# axiom_beta_interface_dummy_v0_13_8a810f7.net
KiCad netlist of a schematic drawn in EAGLE
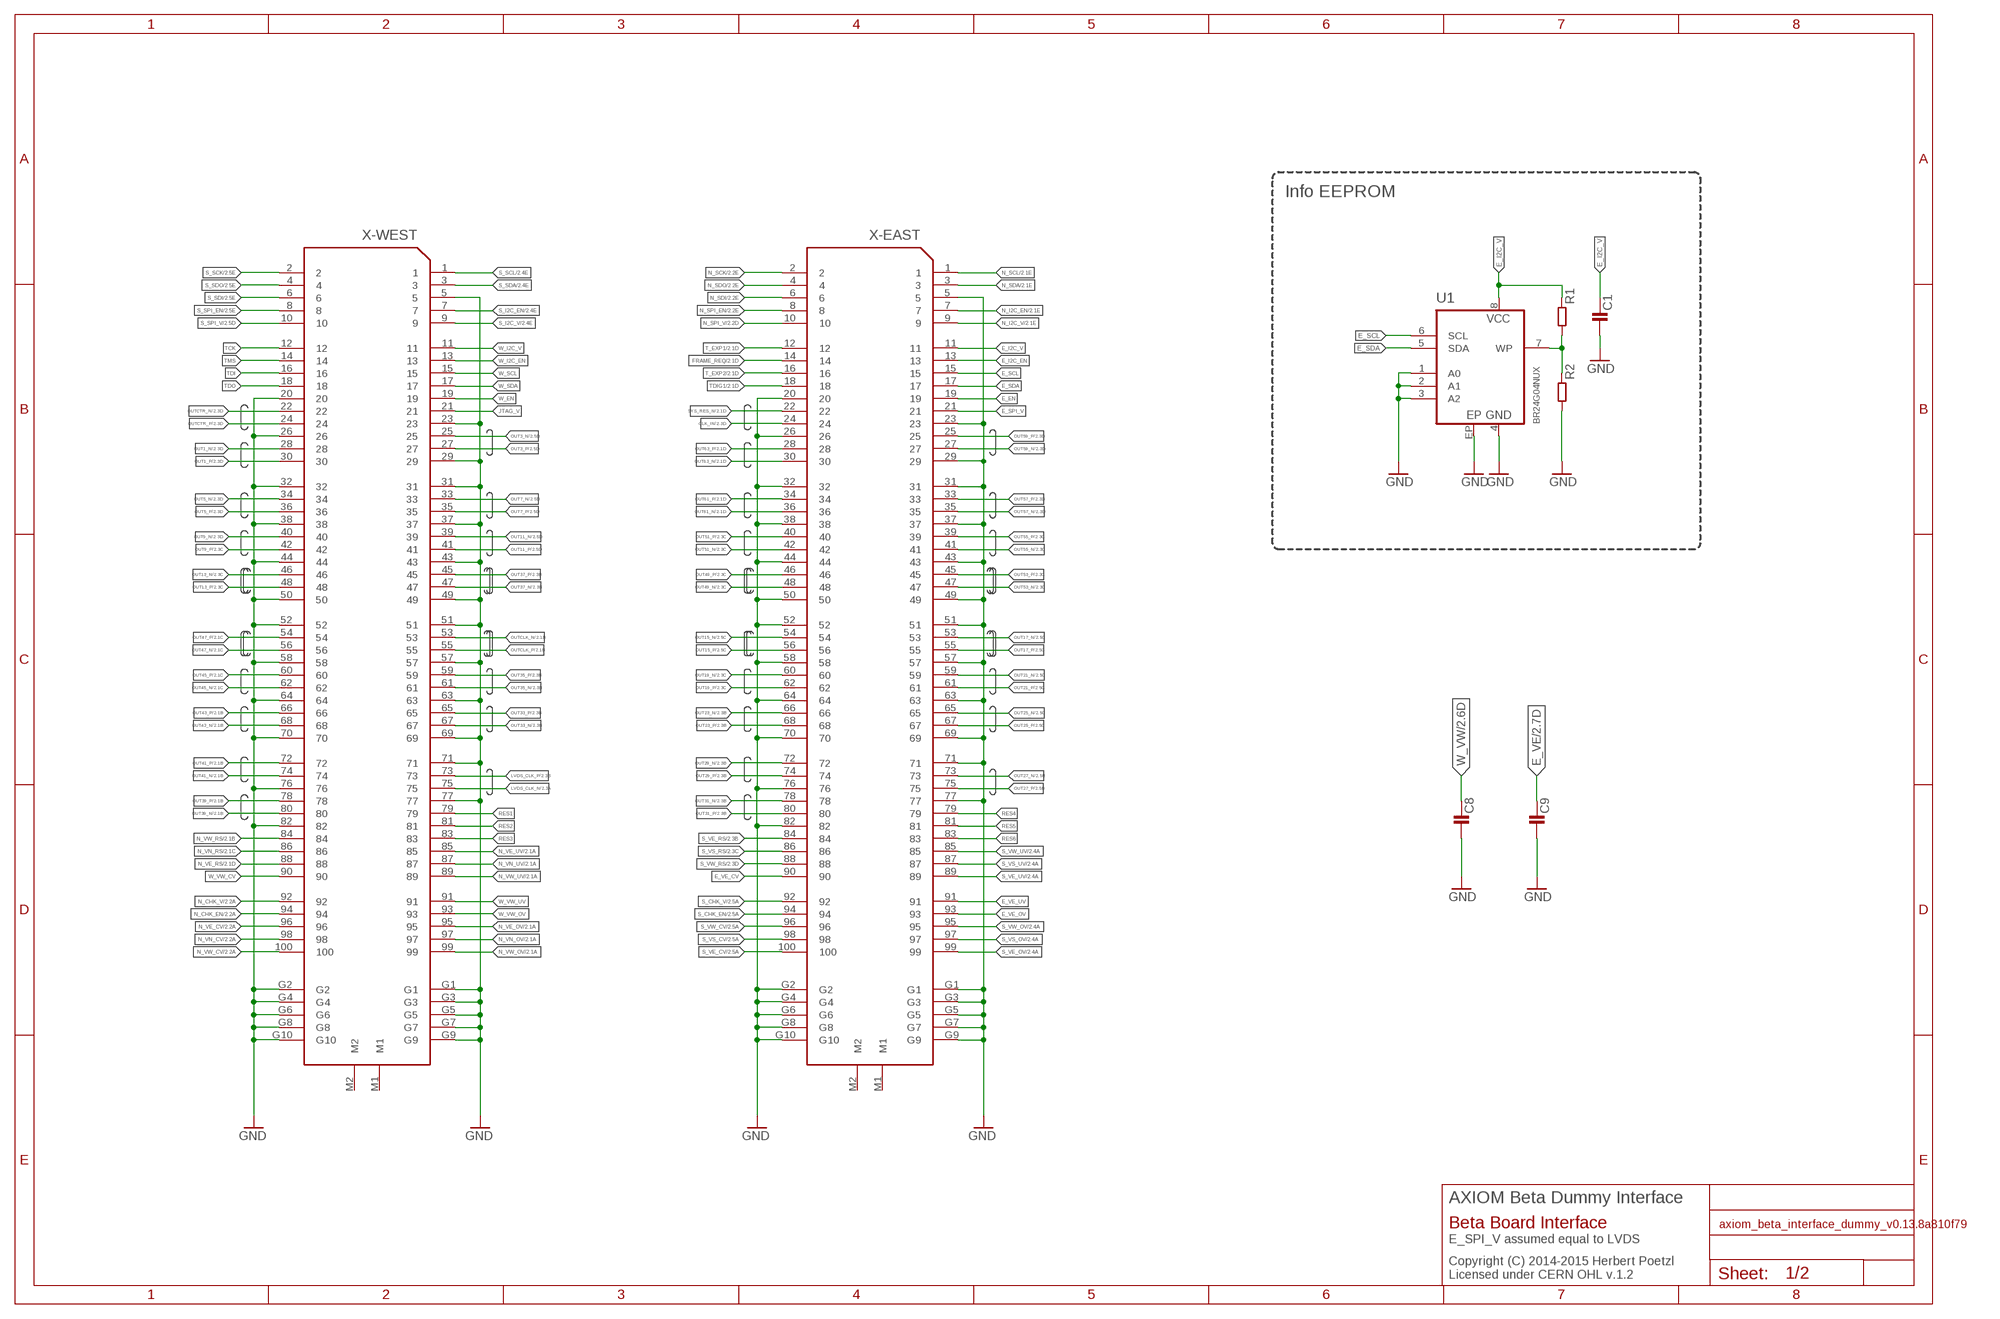
[diagram p0: schematic, sheet 1]
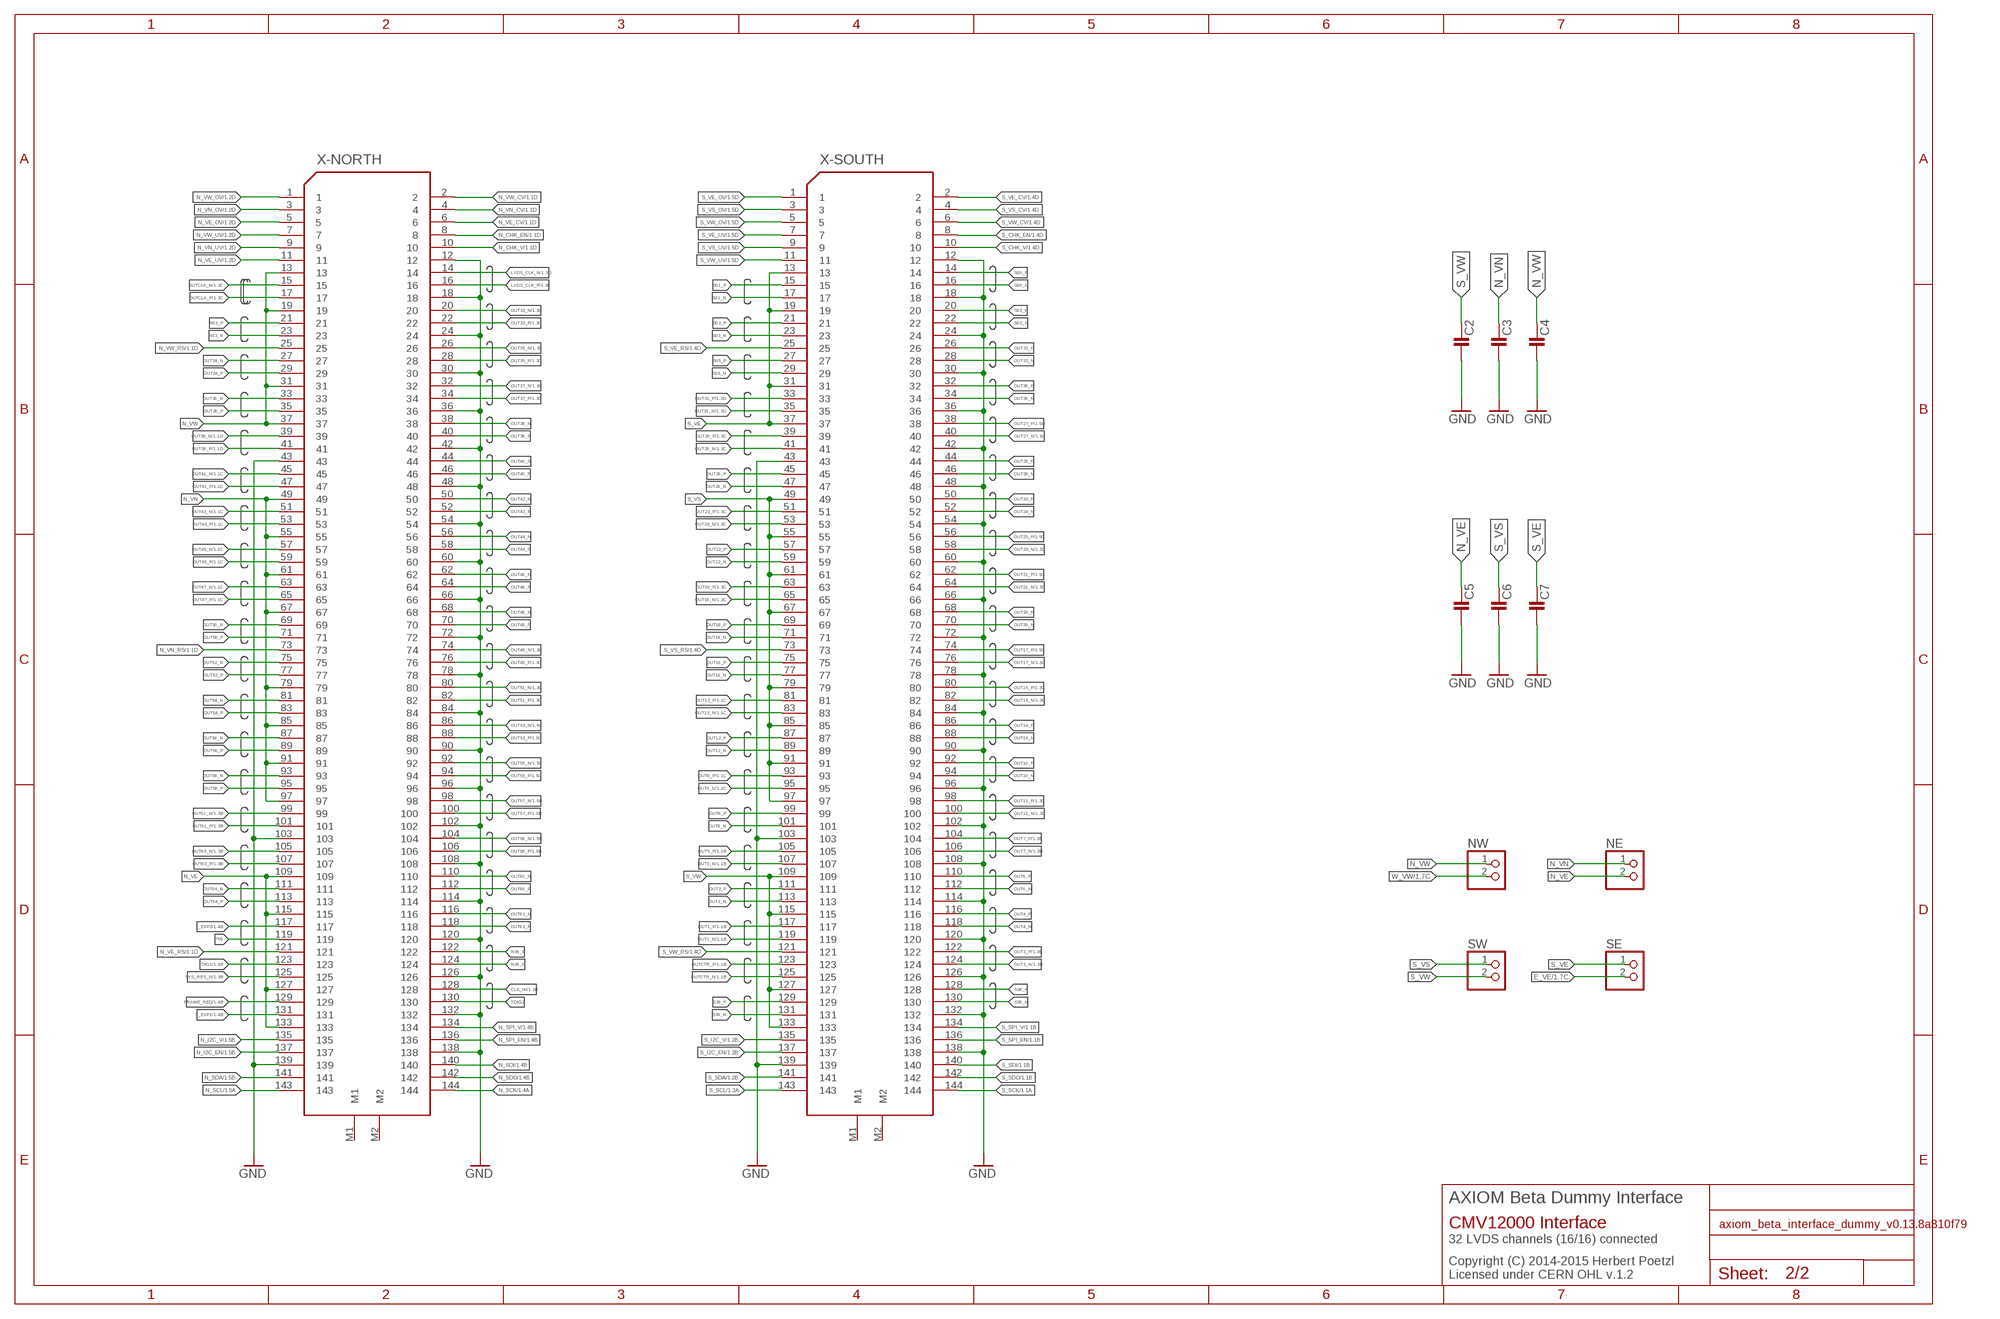
[diagram p1: schematic, sheet 2]

(export (version "E")
  (design (tool "Eeschema 10.0.6"))
  (components
    (comp (ref "C2")
      (value "C0805-B")
      (footprint "eagle-import:0805-B")
      (libsource (lib "eagle-import") (part "C0805-B"))
    )
    (comp (ref "C3")
      (value "C0805-B")
      (footprint "eagle-import:0805-B")
      (libsource (lib "eagle-import") (part "C0805-B"))
    )
    (comp (ref "C4")
      (value "C0805-B")
      (footprint "eagle-import:0805-B")
      (libsource (lib "eagle-import") (part "C0805-B"))
    )
    (comp (ref "C5")
      (value "C0805-B")
      (footprint "eagle-import:0805-B")
      (libsource (lib "eagle-import") (part "C0805-B"))
    )
    (comp (ref "C6")
      (value "C0805-B")
      (footprint "eagle-import:0805-B")
      (libsource (lib "eagle-import") (part "C0805-B"))
    )
    (comp (ref "C7")
      (value "C0805-B")
      (footprint "eagle-import:0805-B")
      (libsource (lib "eagle-import") (part "C0805-B"))
    )
    (comp (ref "NE")
      (value "PINHD-1X02_2.54")
      (footprint "eagle-import:1X02")
      (libsource (lib "eagle-import") (part "PINHD-1X02_2.54"))
    )
    (comp (ref "NW")
      (value "PINHD-1X02_2.54")
      (footprint "eagle-import:1X02")
      (libsource (lib "eagle-import") (part "PINHD-1X02_2.54"))
    )
    (comp (ref "SE")
      (value "PINHD-1X02_2.54")
      (footprint "eagle-import:1X02")
      (libsource (lib "eagle-import") (part "PINHD-1X02_2.54"))
    )
    (comp (ref "SW")
      (value "PINHD-1X02_2.54")
      (footprint "eagle-import:1X02")
      (libsource (lib "eagle-import") (part "PINHD-1X02_2.54"))
    )
    (comp (ref "X-NORTH")
      (value "FX10-144S")
      (footprint "eagle-import:FX10A-144S")
      (libsource (lib "eagle-import") (part "FX10-144S"))
    )
    (comp (ref "X-SOUTH")
      (value "FX10-144S")
      (footprint "eagle-import:FX10A-144S")
      (libsource (lib "eagle-import") (part "FX10-144S"))
    )
    (comp (ref "C1")
      (value "C0402-B")
      (footprint "eagle-import:0402-B")
      (libsource (lib "eagle-import") (part "C0402-B"))
    )
    (comp (ref "C8")
      (value "C0805-B")
      (footprint "eagle-import:0805-B")
      (libsource (lib "eagle-import") (part "C0805-B"))
    )
    (comp (ref "C9")
      (value "C0805-B")
      (footprint "eagle-import:0805-B")
      (libsource (lib "eagle-import") (part "C0805-B"))
    )
    (comp (ref "R1")
      (value "R0402-B")
      (footprint "eagle-import:0402-B")
      (libsource (lib "eagle-import") (part "R0402-B"))
    )
    (comp (ref "R2")
      (value "R0402-B")
      (footprint "eagle-import:0402-B")
      (libsource (lib "eagle-import") (part "R0402-B"))
    )
    (comp (ref "U1")
      (value "BR24G04NUX")
      (footprint "eagle-import:DFN200X300X100-9N")
      (libsource (lib "eagle-import") (part "BR24G04NUX"))
    )
    (comp (ref "X-EAST")
      (value "FX10-100/10P")
      (footprint "eagle-import:FX10A-100P_10")
      (libsource (lib "eagle-import") (part "FX10-100/10P"))
    )
    (comp (ref "X-WEST")
      (value "FX10-100/10P")
      (footprint "eagle-import:FX10A-100P_10")
      (libsource (lib "eagle-import") (part "FX10-100/10P"))
    )
  )
  (nets
    (net (code "1") (name "CLK_IN") (class "Default")
      (node (ref "X-EAST") (pin "24") (pinfunction "24_24") (pintype "bidirectional"))
      (node (ref "X-NORTH") (pin "128") (pinfunction "128_128") (pintype "bidirectional"))
    )
    (net (code "2") (name "E_EN") (class "Default")
      (node (ref "X-EAST") (pin "19") (pinfunction "19_19") (pintype "bidirectional"))
    )
    (net (code "3") (name "E_I2C_EN") (class "Default")
      (node (ref "X-EAST") (pin "13") (pinfunction "13_13") (pintype "bidirectional"))
    )
    (net (code "4") (name "E_I2C_V") (class "Default")
      (node (ref "C1") (pin "1") (pinfunction "1_1") (pintype "passive"))
      (node (ref "R1") (pin "1") (pinfunction "1_1") (pintype "passive"))
      (node (ref "U1") (pin "8") (pinfunction "VCC_8") (pintype "power_in"))
      (node (ref "X-EAST") (pin "11") (pinfunction "11_11") (pintype "bidirectional"))
    )
    (net (code "5") (name "E_SCL") (class "Default")
      (node (ref "U1") (pin "6") (pinfunction "SCL_6") (pintype "input"))
      (node (ref "X-EAST") (pin "15") (pinfunction "15_15") (pintype "bidirectional"))
    )
    (net (code "6") (name "E_SDA") (class "Default")
      (node (ref "U1") (pin "5") (pinfunction "SDA_5") (pintype "bidirectional"))
      (node (ref "X-EAST") (pin "17") (pinfunction "17_17") (pintype "bidirectional"))
    )
    (net (code "7") (name "E_SPI_V") (class "Default")
      (node (ref "X-EAST") (pin "21") (pinfunction "21_21") (pintype "bidirectional"))
    )
    (net (code "8") (name "E_VE") (class "Default")
      (node (ref "C9") (pin "1") (pinfunction "1_1") (pintype "passive"))
      (node (ref "SE") (pin "2") (pinfunction "2_2") (pintype "passive"))
    )
    (net (code "9") (name "E_VE_CV") (class "Default")
      (node (ref "X-EAST") (pin "90") (pinfunction "90_90") (pintype "bidirectional"))
    )
    (net (code "10") (name "E_VE_OV") (class "Default")
      (node (ref "X-EAST") (pin "93") (pinfunction "93_93") (pintype "bidirectional"))
    )
    (net (code "11") (name "E_VE_UV") (class "Default")
      (node (ref "X-EAST") (pin "91") (pinfunction "91_91") (pintype "bidirectional"))
    )
    (net (code "12") (name "FRAME_REQ") (class "Default")
      (node (ref "X-EAST") (pin "14") (pinfunction "14_14") (pintype "bidirectional"))
      (node (ref "X-NORTH") (pin "129") (pinfunction "129_129") (pintype "bidirectional"))
    )
    (net (code "13") (name "GND") (class "Default")
      (node (ref "C1") (pin "2") (pinfunction "2_2") (pintype "passive"))
      (node (ref "C2") (pin "2") (pinfunction "2_2") (pintype "passive"))
      (node (ref "C3") (pin "2") (pinfunction "2_2") (pintype "passive"))
      (node (ref "C4") (pin "2") (pinfunction "2_2") (pintype "passive"))
      (node (ref "C5") (pin "2") (pinfunction "2_2") (pintype "passive"))
      (node (ref "C6") (pin "2") (pinfunction "2_2") (pintype "passive"))
      (node (ref "C7") (pin "2") (pinfunction "2_2") (pintype "passive"))
      (node (ref "C8") (pin "2") (pinfunction "2_2") (pintype "passive"))
      (node (ref "C9") (pin "2") (pinfunction "2_2") (pintype "passive"))
      (node (ref "R2") (pin "2") (pinfunction "2_2") (pintype "passive"))
      (node (ref "U1") (pin "1") (pinfunction "A0_1") (pintype "input"))
      (node (ref "U1") (pin "2") (pinfunction "A1_2") (pintype "input"))
      (node (ref "U1") (pin "3") (pinfunction "A2_3") (pintype "input"))
      (node (ref "U1") (pin "4") (pinfunction "GND_4") (pintype "passive"))
      (node (ref "U1") (pin "EP") (pinfunction "EP_EP") (pintype "passive"))
      (node (ref "X-EAST") (pin "20") (pinfunction "20_20") (pintype "bidirectional"))
      (node (ref "X-EAST") (pin "23") (pinfunction "23_23") (pintype "bidirectional"))
      (node (ref "X-EAST") (pin "26") (pinfunction "26_26") (pintype "bidirectional"))
      (node (ref "X-EAST") (pin "29") (pinfunction "29_29") (pintype "bidirectional"))
      (node (ref "X-EAST") (pin "31") (pinfunction "31_31") (pintype "bidirectional"))
      (node (ref "X-EAST") (pin "32") (pinfunction "32_32") (pintype "bidirectional"))
      (node (ref "X-EAST") (pin "37") (pinfunction "37_37") (pintype "bidirectional"))
      (node (ref "X-EAST") (pin "38") (pinfunction "38_38") (pintype "bidirectional"))
      (node (ref "X-EAST") (pin "43") (pinfunction "43_43") (pintype "bidirectional"))
      (node (ref "X-EAST") (pin "44") (pinfunction "44_44") (pintype "bidirectional"))
      (node (ref "X-EAST") (pin "49") (pinfunction "49_49") (pintype "bidirectional"))
      (node (ref "X-EAST") (pin "5") (pinfunction "5_5") (pintype "bidirectional"))
      (node (ref "X-EAST") (pin "50") (pinfunction "50_50") (pintype "bidirectional"))
      (node (ref "X-EAST") (pin "51") (pinfunction "51_51") (pintype "bidirectional"))
      (node (ref "X-EAST") (pin "52") (pinfunction "52_52") (pintype "bidirectional"))
      (node (ref "X-EAST") (pin "57") (pinfunction "57_57") (pintype "bidirectional"))
      (node (ref "X-EAST") (pin "58") (pinfunction "58_58") (pintype "bidirectional"))
      (node (ref "X-EAST") (pin "63") (pinfunction "63_63") (pintype "bidirectional"))
      (node (ref "X-EAST") (pin "64") (pinfunction "64_64") (pintype "bidirectional"))
      (node (ref "X-EAST") (pin "69") (pinfunction "69_69") (pintype "bidirectional"))
      (node (ref "X-EAST") (pin "70") (pinfunction "70_70") (pintype "bidirectional"))
      (node (ref "X-EAST") (pin "71") (pinfunction "71_71") (pintype "bidirectional"))
      (node (ref "X-EAST") (pin "76") (pinfunction "76_76") (pintype "bidirectional"))
      (node (ref "X-EAST") (pin "77") (pinfunction "77_77") (pintype "bidirectional"))
      (node (ref "X-EAST") (pin "82") (pinfunction "82_82") (pintype "bidirectional"))
      (node (ref "X-EAST") (pin "G1") (pinfunction "G1_G1") (pintype "bidirectional"))
      (node (ref "X-EAST") (pin "G10") (pinfunction "G10_G10") (pintype "bidirectional"))
      (node (ref "X-EAST") (pin "G2") (pinfunction "G2_G2") (pintype "bidirectional"))
      (node (ref "X-EAST") (pin "G3") (pinfunction "G3_G3") (pintype "bidirectional"))
      (node (ref "X-EAST") (pin "G4") (pinfunction "G4_G4") (pintype "bidirectional"))
      (node (ref "X-EAST") (pin "G5") (pinfunction "G5_G5") (pintype "bidirectional"))
      (node (ref "X-EAST") (pin "G6") (pinfunction "G6_G6") (pintype "bidirectional"))
      (node (ref "X-EAST") (pin "G7") (pinfunction "G7_G7") (pintype "bidirectional"))
      (node (ref "X-EAST") (pin "G8") (pinfunction "G8_G8") (pintype "bidirectional"))
      (node (ref "X-EAST") (pin "G9") (pinfunction "G9_G9") (pintype "bidirectional"))
      (node (ref "X-NORTH") (pin "102") (pinfunction "102_102") (pintype "bidirectional"))
      (node (ref "X-NORTH") (pin "103") (pinfunction "103_103") (pintype "bidirectional"))
      (node (ref "X-NORTH") (pin "108") (pinfunction "108_108") (pintype "bidirectional"))
      (node (ref "X-NORTH") (pin "114") (pinfunction "114_114") (pintype "bidirectional"))
      (node (ref "X-NORTH") (pin "12") (pinfunction "12_12") (pintype "bidirectional"))
      (node (ref "X-NORTH") (pin "120") (pinfunction "120_120") (pintype "bidirectional"))
      (node (ref "X-NORTH") (pin "126") (pinfunction "126_126") (pintype "bidirectional"))
      (node (ref "X-NORTH") (pin "132") (pinfunction "132_132") (pintype "bidirectional"))
      (node (ref "X-NORTH") (pin "138") (pinfunction "138_138") (pintype "bidirectional"))
      (node (ref "X-NORTH") (pin "139") (pinfunction "139_139") (pintype "bidirectional"))
      (node (ref "X-NORTH") (pin "18") (pinfunction "18_18") (pintype "bidirectional"))
      (node (ref "X-NORTH") (pin "24") (pinfunction "24_24") (pintype "bidirectional"))
      (node (ref "X-NORTH") (pin "30") (pinfunction "30_30") (pintype "bidirectional"))
      (node (ref "X-NORTH") (pin "36") (pinfunction "36_36") (pintype "bidirectional"))
      (node (ref "X-NORTH") (pin "42") (pinfunction "42_42") (pintype "bidirectional"))
      (node (ref "X-NORTH") (pin "43") (pinfunction "43_43") (pintype "bidirectional"))
      (node (ref "X-NORTH") (pin "48") (pinfunction "48_48") (pintype "bidirectional"))
      (node (ref "X-NORTH") (pin "54") (pinfunction "54_54") (pintype "bidirectional"))
      (node (ref "X-NORTH") (pin "60") (pinfunction "60_60") (pintype "bidirectional"))
      (node (ref "X-NORTH") (pin "66") (pinfunction "66_66") (pintype "bidirectional"))
      (node (ref "X-NORTH") (pin "72") (pinfunction "72_72") (pintype "bidirectional"))
      (node (ref "X-NORTH") (pin "78") (pinfunction "78_78") (pintype "bidirectional"))
      (node (ref "X-NORTH") (pin "84") (pinfunction "84_84") (pintype "bidirectional"))
      (node (ref "X-NORTH") (pin "90") (pinfunction "90_90") (pintype "bidirectional"))
      (node (ref "X-NORTH") (pin "96") (pinfunction "96_96") (pintype "bidirectional"))
      (node (ref "X-SOUTH") (pin "102") (pinfunction "102_102") (pintype "bidirectional"))
      (node (ref "X-SOUTH") (pin "103") (pinfunction "103_103") (pintype "bidirectional"))
      (node (ref "X-SOUTH") (pin "108") (pinfunction "108_108") (pintype "bidirectional"))
      (node (ref "X-SOUTH") (pin "114") (pinfunction "114_114") (pintype "bidirectional"))
      (node (ref "X-SOUTH") (pin "12") (pinfunction "12_12") (pintype "bidirectional"))
      (node (ref "X-SOUTH") (pin "120") (pinfunction "120_120") (pintype "bidirectional"))
      (node (ref "X-SOUTH") (pin "126") (pinfunction "126_126") (pintype "bidirectional"))
      (node (ref "X-SOUTH") (pin "132") (pinfunction "132_132") (pintype "bidirectional"))
      (node (ref "X-SOUTH") (pin "138") (pinfunction "138_138") (pintype "bidirectional"))
      (node (ref "X-SOUTH") (pin "139") (pinfunction "139_139") (pintype "bidirectional"))
      (node (ref "X-SOUTH") (pin "18") (pinfunction "18_18") (pintype "bidirectional"))
      (node (ref "X-SOUTH") (pin "24") (pinfunction "24_24") (pintype "bidirectional"))
      (node (ref "X-SOUTH") (pin "30") (pinfunction "30_30") (pintype "bidirectional"))
      (node (ref "X-SOUTH") (pin "36") (pinfunction "36_36") (pintype "bidirectional"))
      (node (ref "X-SOUTH") (pin "42") (pinfunction "42_42") (pintype "bidirectional"))
      (node (ref "X-SOUTH") (pin "43") (pinfunction "43_43") (pintype "bidirectional"))
      (node (ref "X-SOUTH") (pin "48") (pinfunction "48_48") (pintype "bidirectional"))
      (node (ref "X-SOUTH") (pin "54") (pinfunction "54_54") (pintype "bidirectional"))
      (node (ref "X-SOUTH") (pin "60") (pinfunction "60_60") (pintype "bidirectional"))
      (node (ref "X-SOUTH") (pin "66") (pinfunction "66_66") (pintype "bidirectional"))
      (node (ref "X-SOUTH") (pin "72") (pinfunction "72_72") (pintype "bidirectional"))
      (node (ref "X-SOUTH") (pin "78") (pinfunction "78_78") (pintype "bidirectional"))
      (node (ref "X-SOUTH") (pin "84") (pinfunction "84_84") (pintype "bidirectional"))
      (node (ref "X-SOUTH") (pin "90") (pinfunction "90_90") (pintype "bidirectional"))
      (node (ref "X-SOUTH") (pin "96") (pinfunction "96_96") (pintype "bidirectional"))
      (node (ref "X-WEST") (pin "20") (pinfunction "20_20") (pintype "bidirectional"))
      (node (ref "X-WEST") (pin "23") (pinfunction "23_23") (pintype "bidirectional"))
      (node (ref "X-WEST") (pin "26") (pinfunction "26_26") (pintype "bidirectional"))
      (node (ref "X-WEST") (pin "29") (pinfunction "29_29") (pintype "bidirectional"))
      (node (ref "X-WEST") (pin "31") (pinfunction "31_31") (pintype "bidirectional"))
      (node (ref "X-WEST") (pin "32") (pinfunction "32_32") (pintype "bidirectional"))
      (node (ref "X-WEST") (pin "37") (pinfunction "37_37") (pintype "bidirectional"))
      (node (ref "X-WEST") (pin "38") (pinfunction "38_38") (pintype "bidirectional"))
      (node (ref "X-WEST") (pin "43") (pinfunction "43_43") (pintype "bidirectional"))
      (node (ref "X-WEST") (pin "44") (pinfunction "44_44") (pintype "bidirectional"))
      (node (ref "X-WEST") (pin "49") (pinfunction "49_49") (pintype "bidirectional"))
      (node (ref "X-WEST") (pin "5") (pinfunction "5_5") (pintype "bidirectional"))
      (node (ref "X-WEST") (pin "50") (pinfunction "50_50") (pintype "bidirectional"))
      (node (ref "X-WEST") (pin "51") (pinfunction "51_51") (pintype "bidirectional"))
      (node (ref "X-WEST") (pin "52") (pinfunction "52_52") (pintype "bidirectional"))
      (node (ref "X-WEST") (pin "57") (pinfunction "57_57") (pintype "bidirectional"))
      (node (ref "X-WEST") (pin "58") (pinfunction "58_58") (pintype "bidirectional"))
      (node (ref "X-WEST") (pin "63") (pinfunction "63_63") (pintype "bidirectional"))
      (node (ref "X-WEST") (pin "64") (pinfunction "64_64") (pintype "bidirectional"))
      (node (ref "X-WEST") (pin "69") (pinfunction "69_69") (pintype "bidirectional"))
      (node (ref "X-WEST") (pin "70") (pinfunction "70_70") (pintype "bidirectional"))
      (node (ref "X-WEST") (pin "71") (pinfunction "71_71") (pintype "bidirectional"))
      (node (ref "X-WEST") (pin "76") (pinfunction "76_76") (pintype "bidirectional"))
      (node (ref "X-WEST") (pin "77") (pinfunction "77_77") (pintype "bidirectional"))
      (node (ref "X-WEST") (pin "82") (pinfunction "82_82") (pintype "bidirectional"))
      (node (ref "X-WEST") (pin "G1") (pinfunction "G1_G1") (pintype "bidirectional"))
      (node (ref "X-WEST") (pin "G10") (pinfunction "G10_G10") (pintype "bidirectional"))
      (node (ref "X-WEST") (pin "G2") (pinfunction "G2_G2") (pintype "bidirectional"))
      (node (ref "X-WEST") (pin "G3") (pinfunction "G3_G3") (pintype "bidirectional"))
      (node (ref "X-WEST") (pin "G4") (pinfunction "G4_G4") (pintype "bidirectional"))
      (node (ref "X-WEST") (pin "G5") (pinfunction "G5_G5") (pintype "bidirectional"))
      (node (ref "X-WEST") (pin "G6") (pinfunction "G6_G6") (pintype "bidirectional"))
      (node (ref "X-WEST") (pin "G7") (pinfunction "G7_G7") (pintype "bidirectional"))
      (node (ref "X-WEST") (pin "G8") (pinfunction "G8_G8") (pintype "bidirectional"))
      (node (ref "X-WEST") (pin "G9") (pinfunction "G9_G9") (pintype "bidirectional"))
    )
    (net (code "14") (name "JTAG_V") (class "Default")
      (node (ref "X-WEST") (pin "21") (pinfunction "21_21") (pintype "bidirectional"))
    )
    (net (code "15") (name "LVDS_CLK_N") (class "Default")
      (node (ref "X-NORTH") (pin "14") (pinfunction "14_14") (pintype "bidirectional"))
      (node (ref "X-WEST") (pin "75") (pinfunction "75_75") (pintype "bidirectional"))
    )
    (net (code "16") (name "LVDS_CLK_P") (class "Default")
      (node (ref "X-NORTH") (pin "16") (pinfunction "16_16") (pintype "bidirectional"))
      (node (ref "X-WEST") (pin "73") (pinfunction "73_73") (pintype "bidirectional"))
    )
    (net (code "17") (name "N03_N") (class "Default")
      (node (ref "X-NORTH") (pin "23") (pinfunction "23_23") (pintype "bidirectional"))
    )
    (net (code "18") (name "N03_P") (class "Default")
      (node (ref "X-NORTH") (pin "21") (pinfunction "21_21") (pintype "bidirectional"))
    )
    (net (code "19") (name "N36_N") (class "Default")
      (node (ref "X-NORTH") (pin "124") (pinfunction "124_124") (pintype "bidirectional"))
    )
    (net (code "20") (name "N36_P") (class "Default")
      (node (ref "X-NORTH") (pin "122") (pinfunction "122_122") (pintype "bidirectional"))
    )
    (net (code "21") (name "N_CHK_EN") (class "Default")
      (node (ref "X-NORTH") (pin "8") (pinfunction "8_8") (pintype "bidirectional"))
      (node (ref "X-WEST") (pin "94") (pinfunction "94_94") (pintype "bidirectional"))
    )
    (net (code "22") (name "N_CHK_V") (class "Default")
      (node (ref "X-NORTH") (pin "10") (pinfunction "10_10") (pintype "bidirectional"))
      (node (ref "X-WEST") (pin "92") (pinfunction "92_92") (pintype "bidirectional"))
    )
    (net (code "23") (name "N_I2C_EN") (class "Default")
      (node (ref "X-EAST") (pin "7") (pinfunction "7_7") (pintype "bidirectional"))
      (node (ref "X-NORTH") (pin "137") (pinfunction "137_137") (pintype "bidirectional"))
    )
    (net (code "24") (name "N_I2C_V") (class "Default")
      (node (ref "X-EAST") (pin "9") (pinfunction "9_9") (pintype "bidirectional"))
      (node (ref "X-NORTH") (pin "135") (pinfunction "135_135") (pintype "bidirectional"))
    )
    (net (code "25") (name "N_SCK") (class "Default")
      (node (ref "X-EAST") (pin "2") (pinfunction "2_2") (pintype "bidirectional"))
      (node (ref "X-NORTH") (pin "144") (pinfunction "144_144") (pintype "bidirectional"))
    )
    (net (code "26") (name "N_SCL") (class "Default")
      (node (ref "X-EAST") (pin "1") (pinfunction "1_1") (pintype "bidirectional"))
      (node (ref "X-NORTH") (pin "143") (pinfunction "143_143") (pintype "bidirectional"))
    )
    (net (code "27") (name "N_SDA") (class "Default")
      (node (ref "X-EAST") (pin "3") (pinfunction "3_3") (pintype "bidirectional"))
      (node (ref "X-NORTH") (pin "141") (pinfunction "141_141") (pintype "bidirectional"))
    )
    (net (code "28") (name "N_SDI") (class "Default")
      (node (ref "X-EAST") (pin "6") (pinfunction "6_6") (pintype "bidirectional"))
      (node (ref "X-NORTH") (pin "140") (pinfunction "140_140") (pintype "bidirectional"))
    )
    (net (code "29") (name "N_SDO") (class "Default")
      (node (ref "X-EAST") (pin "4") (pinfunction "4_4") (pintype "bidirectional"))
      (node (ref "X-NORTH") (pin "142") (pinfunction "142_142") (pintype "bidirectional"))
    )
    (net (code "30") (name "N_SPI_EN") (class "Default")
      (node (ref "X-EAST") (pin "8") (pinfunction "8_8") (pintype "bidirectional"))
      (node (ref "X-NORTH") (pin "136") (pinfunction "136_136") (pintype "bidirectional"))
    )
    (net (code "31") (name "N_SPI_V") (class "Default")
      (node (ref "X-EAST") (pin "10") (pinfunction "10_10") (pintype "bidirectional"))
      (node (ref "X-NORTH") (pin "134") (pinfunction "134_134") (pintype "bidirectional"))
    )
    (net (code "32") (name "N_VE") (class "Default")
      (node (ref "C5") (pin "1") (pinfunction "1_1") (pintype "passive"))
      (node (ref "NE") (pin "2") (pinfunction "2_2") (pintype "passive"))
      (node (ref "X-NORTH") (pin "109") (pinfunction "109_109") (pintype "bidirectional"))
      (node (ref "X-NORTH") (pin "115") (pinfunction "115_115") (pintype "bidirectional"))
      (node (ref "X-NORTH") (pin "127") (pinfunction "127_127") (pintype "bidirectional"))
      (node (ref "X-NORTH") (pin "133") (pinfunction "133_133") (pintype "bidirectional"))
    )
    (net (code "33") (name "N_VE_CV") (class "Default")
      (node (ref "X-NORTH") (pin "6") (pinfunction "6_6") (pintype "bidirectional"))
      (node (ref "X-WEST") (pin "96") (pinfunction "96_96") (pintype "bidirectional"))
    )
    (net (code "34") (name "N_VE_OV") (class "Default")
      (node (ref "X-NORTH") (pin "5") (pinfunction "5_5") (pintype "bidirectional"))
      (node (ref "X-WEST") (pin "95") (pinfunction "95_95") (pintype "bidirectional"))
    )
    (net (code "35") (name "N_VE_RS") (class "Default")
      (node (ref "X-NORTH") (pin "121") (pinfunction "121_121") (pintype "bidirectional"))
      (node (ref "X-WEST") (pin "88") (pinfunction "88_88") (pintype "bidirectional"))
    )
    (net (code "36") (name "N_VE_UV") (class "Default")
      (node (ref "X-NORTH") (pin "11") (pinfunction "11_11") (pintype "bidirectional"))
      (node (ref "X-WEST") (pin "85") (pinfunction "85_85") (pintype "bidirectional"))
    )
    (net (code "37") (name "N_VN") (class "Default")
      (node (ref "C3") (pin "1") (pinfunction "1_1") (pintype "passive"))
      (node (ref "NE") (pin "1") (pinfunction "1_1") (pintype "passive"))
      (node (ref "X-NORTH") (pin "49") (pinfunction "49_49") (pintype "bidirectional"))
      (node (ref "X-NORTH") (pin "55") (pinfunction "55_55") (pintype "bidirectional"))
      (node (ref "X-NORTH") (pin "61") (pinfunction "61_61") (pintype "bidirectional"))
      (node (ref "X-NORTH") (pin "67") (pinfunction "67_67") (pintype "bidirectional"))
      (node (ref "X-NORTH") (pin "79") (pinfunction "79_79") (pintype "bidirectional"))
      (node (ref "X-NORTH") (pin "85") (pinfunction "85_85") (pintype "bidirectional"))
      (node (ref "X-NORTH") (pin "91") (pinfunction "91_91") (pintype "bidirectional"))
      (node (ref "X-NORTH") (pin "97") (pinfunction "97_97") (pintype "bidirectional"))
    )
    (net (code "38") (name "N_VN_CV") (class "Default")
      (node (ref "X-NORTH") (pin "4") (pinfunction "4_4") (pintype "bidirectional"))
      (node (ref "X-WEST") (pin "98") (pinfunction "98_98") (pintype "bidirectional"))
    )
    (net (code "39") (name "N_VN_OV") (class "Default")
      (node (ref "X-NORTH") (pin "3") (pinfunction "3_3") (pintype "bidirectional"))
      (node (ref "X-WEST") (pin "97") (pinfunction "97_97") (pintype "bidirectional"))
    )
    (net (code "40") (name "N_VN_RS") (class "Default")
      (node (ref "X-NORTH") (pin "73") (pinfunction "73_73") (pintype "bidirectional"))
      (node (ref "X-WEST") (pin "86") (pinfunction "86_86") (pintype "bidirectional"))
    )
    (net (code "41") (name "N_VN_UV") (class "Default")
      (node (ref "X-NORTH") (pin "9") (pinfunction "9_9") (pintype "bidirectional"))
      (node (ref "X-WEST") (pin "87") (pinfunction "87_87") (pintype "bidirectional"))
    )
    (net (code "42") (name "N_VW") (class "Default")
      (node (ref "C4") (pin "1") (pinfunction "1_1") (pintype "passive"))
      (node (ref "NW") (pin "1") (pinfunction "1_1") (pintype "passive"))
      (node (ref "X-NORTH") (pin "13") (pinfunction "13_13") (pintype "bidirectional"))
      (node (ref "X-NORTH") (pin "19") (pinfunction "19_19") (pintype "bidirectional"))
      (node (ref "X-NORTH") (pin "31") (pinfunction "31_31") (pintype "bidirectional"))
      (node (ref "X-NORTH") (pin "37") (pinfunction "37_37") (pintype "bidirectional"))
    )
    (net (code "43") (name "N_VW_CV") (class "Default")
      (node (ref "X-NORTH") (pin "2") (pinfunction "2_2") (pintype "bidirectional"))
      (node (ref "X-WEST") (pin "100") (pinfunction "100_100") (pintype "bidirectional"))
    )
    (net (code "44") (name "N_VW_OV") (class "Default")
      (node (ref "X-NORTH") (pin "1") (pinfunction "1_1") (pintype "bidirectional"))
      (node (ref "X-WEST") (pin "99") (pinfunction "99_99") (pintype "bidirectional"))
    )
    (net (code "45") (name "N_VW_RS") (class "Default")
      (node (ref "X-NORTH") (pin "25") (pinfunction "25_25") (pintype "bidirectional"))
      (node (ref "X-WEST") (pin "84") (pinfunction "84_84") (pintype "bidirectional"))
    )
    (net (code "46") (name "N_VW_UV") (class "Default")
      (node (ref "X-NORTH") (pin "7") (pinfunction "7_7") (pintype "bidirectional"))
      (node (ref "X-WEST") (pin "89") (pinfunction "89_89") (pintype "bidirectional"))
    )
    (net (code "47") (name "Net-(U1-WP)") (class "Default")
      (node (ref "R1") (pin "2") (pinfunction "2_2") (pintype "passive"))
      (node (ref "R2") (pin "1") (pinfunction "1_1") (pintype "passive"))
      (node (ref "U1") (pin "7") (pinfunction "WP_7") (pintype "input"))
    )
    (net (code "48") (name "OUT1_N") (class "Default")
      (node (ref "X-SOUTH") (pin "119") (pinfunction "119_119") (pintype "bidirectional"))
      (node (ref "X-WEST") (pin "28") (pinfunction "28_28") (pintype "bidirectional"))
    )
    (net (code "49") (name "OUT1_P") (class "Default")
      (node (ref "X-SOUTH") (pin "117") (pinfunction "117_117") (pintype "bidirectional"))
      (node (ref "X-WEST") (pin "30") (pinfunction "30_30") (pintype "bidirectional"))
    )
    (net (code "50") (name "OUT2_N") (class "Default")
      (node (ref "X-SOUTH") (pin "113") (pinfunction "113_113") (pintype "bidirectional"))
    )
    (net (code "51") (name "OUT2_P") (class "Default")
      (node (ref "X-SOUTH") (pin "111") (pinfunction "111_111") (pintype "bidirectional"))
    )
    (net (code "52") (name "OUT3_N") (class "Default")
      (node (ref "X-SOUTH") (pin "124") (pinfunction "124_124") (pintype "bidirectional"))
      (node (ref "X-WEST") (pin "25") (pinfunction "25_25") (pintype "bidirectional"))
    )
    (net (code "53") (name "OUT3_P") (class "Default")
      (node (ref "X-SOUTH") (pin "122") (pinfunction "122_122") (pintype "bidirectional"))
      (node (ref "X-WEST") (pin "27") (pinfunction "27_27") (pintype "bidirectional"))
    )
    (net (code "54") (name "OUT4_N") (class "Default")
      (node (ref "X-SOUTH") (pin "118") (pinfunction "118_118") (pintype "bidirectional"))
    )
    (net (code "55") (name "OUT4_P") (class "Default")
      (node (ref "X-SOUTH") (pin "116") (pinfunction "116_116") (pintype "bidirectional"))
    )
    (net (code "56") (name "OUT5_N") (class "Default")
      (node (ref "X-SOUTH") (pin "107") (pinfunction "107_107") (pintype "bidirectional"))
      (node (ref "X-WEST") (pin "34") (pinfunction "34_34") (pintype "bidirectional"))
    )
    (net (code "57") (name "OUT5_P") (class "Default")
      (node (ref "X-SOUTH") (pin "105") (pinfunction "105_105") (pintype "bidirectional"))
      (node (ref "X-WEST") (pin "36") (pinfunction "36_36") (pintype "bidirectional"))
    )
    (net (code "58") (name "OUT6_N") (class "Default")
      (node (ref "X-SOUTH") (pin "112") (pinfunction "112_112") (pintype "bidirectional"))
    )
    (net (code "59") (name "OUT6_P") (class "Default")
      (node (ref "X-SOUTH") (pin "110") (pinfunction "110_110") (pintype "bidirectional"))
    )
    (net (code "60") (name "OUT7_N") (class "Default")
      (node (ref "X-SOUTH") (pin "106") (pinfunction "106_106") (pintype "bidirectional"))
      (node (ref "X-WEST") (pin "33") (pinfunction "33_33") (pintype "bidirectional"))
    )
    (net (code "61") (name "OUT7_P") (class "Default")
      (node (ref "X-SOUTH") (pin "104") (pinfunction "104_104") (pintype "bidirectional"))
      (node (ref "X-WEST") (pin "35") (pinfunction "35_35") (pintype "bidirectional"))
    )
    (net (code "62") (name "OUT8_N") (class "Default")
      (node (ref "X-SOUTH") (pin "101") (pinfunction "101_101") (pintype "bidirectional"))
    )
    (net (code "63") (name "OUT8_P") (class "Default")
      (node (ref "X-SOUTH") (pin "99") (pinfunction "99_99") (pintype "bidirectional"))
    )
    (net (code "64") (name "OUT9_N") (class "Default")
      (node (ref "X-SOUTH") (pin "95") (pinfunction "95_95") (pintype "bidirectional"))
      (node (ref "X-WEST") (pin "40") (pinfunction "40_40") (pintype "bidirectional"))
    )
    (net (code "65") (name "OUT9_P") (class "Default")
      (node (ref "X-SOUTH") (pin "93") (pinfunction "93_93") (pintype "bidirectional"))
      (node (ref "X-WEST") (pin "42") (pinfunction "42_42") (pintype "bidirectional"))
    )
    (net (code "66") (name "OUT10_N") (class "Default")
      (node (ref "X-SOUTH") (pin "94") (pinfunction "94_94") (pintype "bidirectional"))
    )
    (net (code "67") (name "OUT10_P") (class "Default")
      (node (ref "X-SOUTH") (pin "92") (pinfunction "92_92") (pintype "bidirectional"))
    )
    (net (code "68") (name "OUT11_N") (class "Default")
      (node (ref "X-SOUTH") (pin "100") (pinfunction "100_100") (pintype "bidirectional"))
      (node (ref "X-WEST") (pin "39") (pinfunction "39_39") (pintype "bidirectional"))
    )
    (net (code "69") (name "OUT11_P") (class "Default")
      (node (ref "X-SOUTH") (pin "98") (pinfunction "98_98") (pintype "bidirectional"))
      (node (ref "X-WEST") (pin "41") (pinfunction "41_41") (pintype "bidirectional"))
    )
    (net (code "70") (name "OUT12_N") (class "Default")
      (node (ref "X-SOUTH") (pin "89") (pinfunction "89_89") (pintype "bidirectional"))
    )
    (net (code "71") (name "OUT12_P") (class "Default")
      (node (ref "X-SOUTH") (pin "87") (pinfunction "87_87") (pintype "bidirectional"))
    )
    (net (code "72") (name "OUT13_N") (class "Default")
      (node (ref "X-SOUTH") (pin "83") (pinfunction "83_83") (pintype "bidirectional"))
      (node (ref "X-WEST") (pin "46") (pinfunction "46_46") (pintype "bidirectional"))
    )
    (net (code "73") (name "OUT13_P") (class "Default")
      (node (ref "X-SOUTH") (pin "81") (pinfunction "81_81") (pintype "bidirectional"))
      (node (ref "X-WEST") (pin "48") (pinfunction "48_48") (pintype "bidirectional"))
    )
    (net (code "74") (name "OUT14_N") (class "Default")
      (node (ref "X-SOUTH") (pin "88") (pinfunction "88_88") (pintype "bidirectional"))
    )
    (net (code "75") (name "OUT14_P") (class "Default")
      (node (ref "X-SOUTH") (pin "86") (pinfunction "86_86") (pintype "bidirectional"))
    )
    (net (code "76") (name "OUT15_N") (class "Default")
      (node (ref "X-EAST") (pin "54") (pinfunction "54_54") (pintype "bidirectional"))
      (node (ref "X-SOUTH") (pin "82") (pinfunction "82_82") (pintype "bidirectional"))
    )
    (net (code "77") (name "OUT15_P") (class "Default")
      (node (ref "X-EAST") (pin "56") (pinfunction "56_56") (pintype "bidirectional"))
      (node (ref "X-SOUTH") (pin "80") (pinfunction "80_80") (pintype "bidirectional"))
    )
    (net (code "78") (name "OUT16_N") (class "Default")
      (node (ref "X-SOUTH") (pin "77") (pinfunction "77_77") (pintype "bidirectional"))
    )
    (net (code "79") (name "OUT16_P") (class "Default")
      (node (ref "X-SOUTH") (pin "75") (pinfunction "75_75") (pintype "bidirectional"))
    )
    (net (code "80") (name "OUT17_N") (class "Default")
      (node (ref "X-EAST") (pin "53") (pinfunction "53_53") (pintype "bidirectional"))
      (node (ref "X-SOUTH") (pin "76") (pinfunction "76_76") (pintype "bidirectional"))
    )
    (net (code "81") (name "OUT17_P") (class "Default")
      (node (ref "X-EAST") (pin "55") (pinfunction "55_55") (pintype "bidirectional"))
      (node (ref "X-SOUTH") (pin "74") (pinfunction "74_74") (pintype "bidirectional"))
    )
    (net (code "82") (name "OUT18_N") (class "Default")
      (node (ref "X-SOUTH") (pin "71") (pinfunction "71_71") (pintype "bidirectional"))
    )
    (net (code "83") (name "OUT18_P") (class "Default")
      (node (ref "X-SOUTH") (pin "69") (pinfunction "69_69") (pintype "bidirectional"))
    )
    (net (code "84") (name "OUT19_N") (class "Default")
      (node (ref "X-EAST") (pin "60") (pinfunction "60_60") (pintype "bidirectional"))
      (node (ref "X-SOUTH") (pin "65") (pinfunction "65_65") (pintype "bidirectional"))
    )
    (net (code "85") (name "OUT19_P") (class "Default")
      (node (ref "X-EAST") (pin "62") (pinfunction "62_62") (pintype "bidirectional"))
      (node (ref "X-SOUTH") (pin "63") (pinfunction "63_63") (pintype "bidirectional"))
    )
    (net (code "86") (name "OUT20_N") (class "Default")
      (node (ref "X-SOUTH") (pin "70") (pinfunction "70_70") (pintype "bidirectional"))
    )
    (net (code "87") (name "OUT20_P") (class "Default")
      (node (ref "X-SOUTH") (pin "68") (pinfunction "68_68") (pintype "bidirectional"))
    )
    (net (code "88") (name "OUT21_N") (class "Default")
      (node (ref "X-EAST") (pin "59") (pinfunction "59_59") (pintype "bidirectional"))
      (node (ref "X-SOUTH") (pin "64") (pinfunction "64_64") (pintype "bidirectional"))
    )
    (net (code "89") (name "OUT21_P") (class "Default")
      (node (ref "X-EAST") (pin "61") (pinfunction "61_61") (pintype "bidirectional"))
      (node (ref "X-SOUTH") (pin "62") (pinfunction "62_62") (pintype "bidirectional"))
    )
    (net (code "90") (name "OUT22_N") (class "Default")
      (node (ref "X-SOUTH") (pin "59") (pinfunction "59_59") (pintype "bidirectional"))
    )
    (net (code "91") (name "OUT22_P") (class "Default")
      (node (ref "X-SOUTH") (pin "57") (pinfunction "57_57") (pintype "bidirectional"))
    )
    (net (code "92") (name "OUT23_N") (class "Default")
      (node (ref "X-EAST") (pin "66") (pinfunction "66_66") (pintype "bidirectional"))
      (node (ref "X-SOUTH") (pin "53") (pinfunction "53_53") (pintype "bidirectional"))
    )
    (net (code "93") (name "OUT23_P") (class "Default")
      (node (ref "X-EAST") (pin "68") (pinfunction "68_68") (pintype "bidirectional"))
      (node (ref "X-SOUTH") (pin "51") (pinfunction "51_51") (pintype "bidirectional"))
    )
    (net (code "94") (name "OUT24_N") (class "Default")
      (node (ref "X-SOUTH") (pin "52") (pinfunction "52_52") (pintype "bidirectional"))
    )
    (net (code "95") (name "OUT24_P") (class "Default")
      (node (ref "X-SOUTH") (pin "50") (pinfunction "50_50") (pintype "bidirectional"))
    )
    (net (code "96") (name "OUT25_N") (class "Default")
      (node (ref "X-EAST") (pin "65") (pinfunction "65_65") (pintype "bidirectional"))
      (node (ref "X-SOUTH") (pin "58") (pinfunction "58_58") (pintype "bidirectional"))
    )
    (net (code "97") (name "OUT25_P") (class "Default")
      (node (ref "X-EAST") (pin "67") (pinfunction "67_67") (pintype "bidirectional"))
      (node (ref "X-SOUTH") (pin "56") (pinfunction "56_56") (pintype "bidirectional"))
    )
    (net (code "98") (name "OUT26_N") (class "Default")
      (node (ref "X-SOUTH") (pin "47") (pinfunction "47_47") (pintype "bidirectional"))
    )
    (net (code "99") (name "OUT26_P") (class "Default")
      (node (ref "X-SOUTH") (pin "45") (pinfunction "45_45") (pintype "bidirectional"))
    )
    (net (code "100") (name "OUT27_N") (class "Default")
      (node (ref "X-EAST") (pin "73") (pinfunction "73_73") (pintype "bidirectional"))
      (node (ref "X-SOUTH") (pin "40") (pinfunction "40_40") (pintype "bidirectional"))
    )
    (net (code "101") (name "OUT27_P") (class "Default")
      (node (ref "X-EAST") (pin "75") (pinfunction "75_75") (pintype "bidirectional"))
      (node (ref "X-SOUTH") (pin "38") (pinfunction "38_38") (pintype "bidirectional"))
    )
    (net (code "102") (name "OUT28_N") (class "Default")
      (node (ref "X-SOUTH") (pin "46") (pinfunction "46_46") (pintype "bidirectional"))
    )
    (net (code "103") (name "OUT28_P") (class "Default")
      (node (ref "X-SOUTH") (pin "44") (pinfunction "44_44") (pintype "bidirectional"))
    )
    (net (code "104") (name "OUT29_N") (class "Default")
      (node (ref "X-EAST") (pin "72") (pinfunction "72_72") (pintype "bidirectional"))
      (node (ref "X-SOUTH") (pin "41") (pinfunction "41_41") (pintype "bidirectional"))
    )
    (net (code "105") (name "OUT29_P") (class "Default")
      (node (ref "X-EAST") (pin "74") (pinfunction "74_74") (pintype "bidirectional"))
      (node (ref "X-SOUTH") (pin "39") (pinfunction "39_39") (pintype "bidirectional"))
    )
    (net (code "106") (name "OUT30_N") (class "Default")
      (node (ref "X-SOUTH") (pin "34") (pinfunction "34_34") (pintype "bidirectional"))
    )
    (net (code "107") (name "OUT30_P") (class "Default")
      (node (ref "X-SOUTH") (pin "32") (pinfunction "32_32") (pintype "bidirectional"))
    )
    (net (code "108") (name "OUT31_N") (class "Default")
      (node (ref "X-EAST") (pin "78") (pinfunction "78_78") (pintype "bidirectional"))
      (node (ref "X-SOUTH") (pin "35") (pinfunction "35_35") (pintype "bidirectional"))
    )
    (net (code "109") (name "OUT31_P") (class "Default")
      (node (ref "X-EAST") (pin "80") (pinfunction "80_80") (pintype "bidirectional"))
      (node (ref "X-SOUTH") (pin "33") (pinfunction "33_33") (pintype "bidirectional"))
    )
    (net (code "110") (name "OUT32_N") (class "Default")
      (node (ref "X-SOUTH") (pin "28") (pinfunction "28_28") (pintype "bidirectional"))
    )
    (net (code "111") (name "OUT32_P") (class "Default")
      (node (ref "X-SOUTH") (pin "26") (pinfunction "26_26") (pintype "bidirectional"))
    )
    (net (code "112") (name "OUT33_N") (class "Default")
      (node (ref "X-NORTH") (pin "20") (pinfunction "20_20") (pintype "bidirectional"))
      (node (ref "X-WEST") (pin "67") (pinfunction "67_67") (pintype "bidirectional"))
    )
    (net (code "113") (name "OUT33_P") (class "Default")
      (node (ref "X-NORTH") (pin "22") (pinfunction "22_22") (pintype "bidirectional"))
      (node (ref "X-WEST") (pin "65") (pinfunction "65_65") (pintype "bidirectional"))
    )
    (net (code "114") (name "OUT34_N") (class "Default")
      (node (ref "X-NORTH") (pin "27") (pinfunction "27_27") (pintype "bidirectional"))
    )
    (net (code "115") (name "OUT34_P") (class "Default")
      (node (ref "X-NORTH") (pin "29") (pinfunction "29_29") (pintype "bidirectional"))
    )
    (net (code "116") (name "OUT35_N") (class "Default")
      (node (ref "X-NORTH") (pin "26") (pinfunction "26_26") (pintype "bidirectional"))
      (node (ref "X-WEST") (pin "61") (pinfunction "61_61") (pintype "bidirectional"))
    )
    (net (code "117") (name "OUT35_P") (class "Default")
      (node (ref "X-NORTH") (pin "28") (pinfunction "28_28") (pintype "bidirectional"))
      (node (ref "X-WEST") (pin "59") (pinfunction "59_59") (pintype "bidirectional"))
    )
    (net (code "118") (name "OUT36_N") (class "Default")
      (node (ref "X-NORTH") (pin "33") (pinfunction "33_33") (pintype "bidirectional"))
    )
    (net (code "119") (name "OUT36_P") (class "Default")
      (node (ref "X-NORTH") (pin "35") (pinfunction "35_35") (pintype "bidirectional"))
    )
    (net (code "120") (name "OUT37_N") (class "Default")
      (node (ref "X-NORTH") (pin "32") (pinfunction "32_32") (pintype "bidirectional"))
      (node (ref "X-WEST") (pin "47") (pinfunction "47_47") (pintype "bidirectional"))
    )
    (net (code "121") (name "OUT37_P") (class "Default")
      (node (ref "X-NORTH") (pin "34") (pinfunction "34_34") (pintype "bidirectional"))
      (node (ref "X-WEST") (pin "45") (pinfunction "45_45") (pintype "bidirectional"))
    )
    (net (code "122") (name "OUT38_N") (class "Default")
      (node (ref "X-NORTH") (pin "38") (pinfunction "38_38") (pintype "bidirectional"))
    )
    (net (code "123") (name "OUT38_P") (class "Default")
      (node (ref "X-NORTH") (pin "40") (pinfunction "40_40") (pintype "bidirectional"))
    )
    (net (code "124") (name "OUT39_N") (class "Default")
      (node (ref "X-NORTH") (pin "39") (pinfunction "39_39") (pintype "bidirectional"))
      (node (ref "X-WEST") (pin "80") (pinfunction "80_80") (pintype "bidirectional"))
    )
    (net (code "125") (name "OUT39_P") (class "Default")
      (node (ref "X-NORTH") (pin "41") (pinfunction "41_41") (pintype "bidirectional"))
      (node (ref "X-WEST") (pin "78") (pinfunction "78_78") (pintype "bidirectional"))
    )
    (net (code "126") (name "OUT40_N") (class "Default")
      (node (ref "X-NORTH") (pin "44") (pinfunction "44_44") (pintype "bidirectional"))
    )
    (net (code "127") (name "OUT40_P") (class "Default")
      (node (ref "X-NORTH") (pin "46") (pinfunction "46_46") (pintype "bidirectional"))
    )
    (net (code "128") (name "OUT41_N") (class "Default")
      (node (ref "X-NORTH") (pin "45") (pinfunction "45_45") (pintype "bidirectional"))
      (node (ref "X-WEST") (pin "74") (pinfunction "74_74") (pintype "bidirectional"))
    )
    (net (code "129") (name "OUT41_P") (class "Default")
      (node (ref "X-NORTH") (pin "47") (pinfunction "47_47") (pintype "bidirectional"))
      (node (ref "X-WEST") (pin "72") (pinfunction "72_72") (pintype "bidirectional"))
    )
    (net (code "130") (name "OUT42_N") (class "Default")
      (node (ref "X-NORTH") (pin "50") (pinfunction "50_50") (pintype "bidirectional"))
    )
    (net (code "131") (name "OUT42_P") (class "Default")
      (node (ref "X-NORTH") (pin "52") (pinfunction "52_52") (pintype "bidirectional"))
    )
    (net (code "132") (name "OUT43_N") (class "Default")
      (node (ref "X-NORTH") (pin "51") (pinfunction "51_51") (pintype "bidirectional"))
      (node (ref "X-WEST") (pin "68") (pinfunction "68_68") (pintype "bidirectional"))
    )
    (net (code "133") (name "OUT43_P") (class "Default")
      (node (ref "X-NORTH") (pin "53") (pinfunction "53_53") (pintype "bidirectional"))
      (node (ref "X-WEST") (pin "66") (pinfunction "66_66") (pintype "bidirectional"))
    )
    (net (code "134") (name "OUT44_N") (class "Default")
      (node (ref "X-NORTH") (pin "56") (pinfunction "56_56") (pintype "bidirectional"))
    )
    (net (code "135") (name "OUT44_P") (class "Default")
      (node (ref "X-NORTH") (pin "58") (pinfunction "58_58") (pintype "bidirectional"))
    )
    (net (code "136") (name "OUT45_N") (class "Default")
      (node (ref "X-NORTH") (pin "57") (pinfunction "57_57") (pintype "bidirectional"))
      (node (ref "X-WEST") (pin "62") (pinfunction "62_62") (pintype "bidirectional"))
    )
    (net (code "137") (name "OUT45_P") (class "Default")
      (node (ref "X-NORTH") (pin "59") (pinfunction "59_59") (pintype "bidirectional"))
      (node (ref "X-WEST") (pin "60") (pinfunction "60_60") (pintype "bidirectional"))
    )
    (net (code "138") (name "OUT46_N") (class "Default")
      (node (ref "X-NORTH") (pin "62") (pinfunction "62_62") (pintype "bidirectional"))
    )
    (net (code "139") (name "OUT46_P") (class "Default")
      (node (ref "X-NORTH") (pin "64") (pinfunction "64_64") (pintype "bidirectional"))
    )
    (net (code "140") (name "OUT47_N") (class "Default")
      (node (ref "X-NORTH") (pin "63") (pinfunction "63_63") (pintype "bidirectional"))
      (node (ref "X-WEST") (pin "56") (pinfunction "56_56") (pintype "bidirectional"))
    )
    (net (code "141") (name "OUT47_P") (class "Default")
      (node (ref "X-NORTH") (pin "65") (pinfunction "65_65") (pintype "bidirectional"))
      (node (ref "X-WEST") (pin "54") (pinfunction "54_54") (pintype "bidirectional"))
    )
    (net (code "142") (name "OUT48_N") (class "Default")
      (node (ref "X-NORTH") (pin "68") (pinfunction "68_68") (pintype "bidirectional"))
    )
    (net (code "143") (name "OUT48_P") (class "Default")
      (node (ref "X-NORTH") (pin "70") (pinfunction "70_70") (pintype "bidirectional"))
    )
    (net (code "144") (name "OUT49_N") (class "Default")
      (node (ref "X-EAST") (pin "48") (pinfunction "48_48") (pintype "bidirectional"))
      (node (ref "X-NORTH") (pin "74") (pinfunction "74_74") (pintype "bidirectional"))
    )
    (net (code "145") (name "OUT49_P") (class "Default")
      (node (ref "X-EAST") (pin "46") (pinfunction "46_46") (pintype "bidirectional"))
      (node (ref "X-NORTH") (pin "76") (pinfunction "76_76") (pintype "bidirectional"))
    )
    (net (code "146") (name "OUT50_N") (class "Default")
      (node (ref "X-NORTH") (pin "69") (pinfunction "69_69") (pintype "bidirectional"))
    )
    (net (code "147") (name "OUT50_P") (class "Default")
      (node (ref "X-NORTH") (pin "71") (pinfunction "71_71") (pintype "bidirectional"))
    )
    (net (code "148") (name "OUT51_N") (class "Default")
      (node (ref "X-EAST") (pin "42") (pinfunction "42_42") (pintype "bidirectional"))
      (node (ref "X-NORTH") (pin "80") (pinfunction "80_80") (pintype "bidirectional"))
    )
    (net (code "149") (name "OUT51_P") (class "Default")
      (node (ref "X-EAST") (pin "40") (pinfunction "40_40") (pintype "bidirectional"))
      (node (ref "X-NORTH") (pin "82") (pinfunction "82_82") (pintype "bidirectional"))
    )
    (net (code "150") (name "OUT52_N") (class "Default")
      (node (ref "X-NORTH") (pin "75") (pinfunction "75_75") (pintype "bidirectional"))
    )
    (net (code "151") (name "OUT52_P") (class "Default")
      (node (ref "X-NORTH") (pin "77") (pinfunction "77_77") (pintype "bidirectional"))
    )
    (net (code "152") (name "OUT53_N") (class "Default")
      (node (ref "X-EAST") (pin "47") (pinfunction "47_47") (pintype "bidirectional"))
      (node (ref "X-NORTH") (pin "86") (pinfunction "86_86") (pintype "bidirectional"))
    )
    (net (code "153") (name "OUT53_P") (class "Default")
      (node (ref "X-EAST") (pin "45") (pinfunction "45_45") (pintype "bidirectional"))
      (node (ref "X-NORTH") (pin "88") (pinfunction "88_88") (pintype "bidirectional"))
    )
    (net (code "154") (name "OUT54_N") (class "Default")
      (node (ref "X-NORTH") (pin "81") (pinfunction "81_81") (pintype "bidirectional"))
    )
    (net (code "155") (name "OUT54_P") (class "Default")
      (node (ref "X-NORTH") (pin "83") (pinfunction "83_83") (pintype "bidirectional"))
    )
    (net (code "156") (name "OUT55_N") (class "Default")
      (node (ref "X-EAST") (pin "41") (pinfunction "41_41") (pintype "bidirectional"))
      (node (ref "X-NORTH") (pin "92") (pinfunction "92_92") (pintype "bidirectional"))
    )
    (net (code "157") (name "OUT55_P") (class "Default")
      (node (ref "X-EAST") (pin "39") (pinfunction "39_39") (pintype "bidirectional"))
      (node (ref "X-NORTH") (pin "94") (pinfunction "94_94") (pintype "bidirectional"))
    )
    (net (code "158") (name "OUT56_N") (class "Default")
      (node (ref "X-NORTH") (pin "87") (pinfunction "87_87") (pintype "bidirectional"))
    )
    (net (code "159") (name "OUT56_P") (class "Default")
      (node (ref "X-NORTH") (pin "89") (pinfunction "89_89") (pintype "bidirectional"))
    )
    (net (code "160") (name "OUT57_N") (class "Default")
      (node (ref "X-EAST") (pin "35") (pinfunction "35_35") (pintype "bidirectional"))
      (node (ref "X-NORTH") (pin "98") (pinfunction "98_98") (pintype "bidirectional"))
    )
    (net (code "161") (name "OUT57_P") (class "Default")
      (node (ref "X-EAST") (pin "33") (pinfunction "33_33") (pintype "bidirectional"))
      (node (ref "X-NORTH") (pin "100") (pinfunction "100_100") (pintype "bidirectional"))
    )
    (net (code "162") (name "OUT58_N") (class "Default")
      (node (ref "X-NORTH") (pin "93") (pinfunction "93_93") (pintype "bidirectional"))
    )
    (net (code "163") (name "OUT58_P") (class "Default")
      (node (ref "X-NORTH") (pin "95") (pinfunction "95_95") (pintype "bidirectional"))
    )
    (net (code "164") (name "OUT59_N") (class "Default")
      (node (ref "X-EAST") (pin "27") (pinfunction "27_27") (pintype "bidirectional"))
      (node (ref "X-NORTH") (pin "104") (pinfunction "104_104") (pintype "bidirectional"))
    )
    (net (code "165") (name "OUT59_P") (class "Default")
      (node (ref "X-EAST") (pin "25") (pinfunction "25_25") (pintype "bidirectional"))
      (node (ref "X-NORTH") (pin "106") (pinfunction "106_106") (pintype "bidirectional"))
    )
    (net (code "166") (name "OUT60_N") (class "Default")
      (node (ref "X-NORTH") (pin "110") (pinfunction "110_110") (pintype "bidirectional"))
    )
    (net (code "167") (name "OUT60_P") (class "Default")
      (node (ref "X-NORTH") (pin "112") (pinfunction "112_112") (pintype "bidirectional"))
    )
    (net (code "168") (name "OUT61_N") (class "Default")
      (node (ref "X-EAST") (pin "36") (pinfunction "36_36") (pintype "bidirectional"))
      (node (ref "X-NORTH") (pin "99") (pinfunction "99_99") (pintype "bidirectional"))
    )
    (net (code "169") (name "OUT61_P") (class "Default")
      (node (ref "X-EAST") (pin "34") (pinfunction "34_34") (pintype "bidirectional"))
      (node (ref "X-NORTH") (pin "101") (pinfunction "101_101") (pintype "bidirectional"))
    )
    (net (code "170") (name "OUT62_N") (class "Default")
      (node (ref "X-NORTH") (pin "116") (pinfunction "116_116") (pintype "bidirectional"))
    )
    (net (code "171") (name "OUT62_P") (class "Default")
      (node (ref "X-NORTH") (pin "118") (pinfunction "118_118") (pintype "bidirectional"))
    )
    (net (code "172") (name "OUT63_N") (class "Default")
      (node (ref "X-EAST") (pin "30") (pinfunction "30_30") (pintype "bidirectional"))
      (node (ref "X-NORTH") (pin "105") (pinfunction "105_105") (pintype "bidirectional"))
    )
    (net (code "173") (name "OUT63_P") (class "Default")
      (node (ref "X-EAST") (pin "28") (pinfunction "28_28") (pintype "bidirectional"))
      (node (ref "X-NORTH") (pin "107") (pinfunction "107_107") (pintype "bidirectional"))
    )
    (net (code "174") (name "OUT64_N") (class "Default")
      (node (ref "X-NORTH") (pin "111") (pinfunction "111_111") (pintype "bidirectional"))
    )
    (net (code "175") (name "OUT64_P") (class "Default")
      (node (ref "X-NORTH") (pin "113") (pinfunction "113_113") (pintype "bidirectional"))
    )
    (net (code "176") (name "OUTCLK_N") (class "Default")
      (node (ref "X-NORTH") (pin "15") (pinfunction "15_15") (pintype "bidirectional"))
      (node (ref "X-WEST") (pin "53") (pinfunction "53_53") (pintype "bidirectional"))
    )
    (net (code "177") (name "OUTCLK_P") (class "Default")
      (node (ref "X-NORTH") (pin "17") (pinfunction "17_17") (pintype "bidirectional"))
      (node (ref "X-WEST") (pin "55") (pinfunction "55_55") (pintype "bidirectional"))
    )
    (net (code "178") (name "OUTCTR_N") (class "Default")
      (node (ref "X-SOUTH") (pin "125") (pinfunction "125_125") (pintype "bidirectional"))
      (node (ref "X-WEST") (pin "22") (pinfunction "22_22") (pintype "bidirectional"))
    )
    (net (code "179") (name "OUTCTR_P") (class "Default")
      (node (ref "X-SOUTH") (pin "123") (pinfunction "123_123") (pintype "bidirectional"))
      (node (ref "X-WEST") (pin "24") (pinfunction "24_24") (pintype "bidirectional"))
    )
    (net (code "180") (name "RES1") (class "Default")
      (node (ref "X-WEST") (pin "79") (pinfunction "79_79") (pintype "bidirectional"))
    )
    (net (code "181") (name "RES2") (class "Default")
      (node (ref "X-WEST") (pin "81") (pinfunction "81_81") (pintype "bidirectional"))
    )
    (net (code "182") (name "RES3") (class "Default")
      (node (ref "X-WEST") (pin "83") (pinfunction "83_83") (pintype "bidirectional"))
    )
    (net (code "183") (name "RES4") (class "Default")
      (node (ref "X-EAST") (pin "79") (pinfunction "79_79") (pintype "bidirectional"))
    )
    (net (code "184") (name "RES5") (class "Default")
      (node (ref "X-EAST") (pin "81") (pinfunction "81_81") (pintype "bidirectional"))
    )
    (net (code "185") (name "RES6") (class "Default")
      (node (ref "X-EAST") (pin "83") (pinfunction "83_83") (pintype "bidirectional"))
    )
    (net (code "186") (name "S00_N") (class "Default")
      (node (ref "X-SOUTH") (pin "16") (pinfunction "16_16") (pintype "bidirectional"))
    )
    (net (code "187") (name "S00_P") (class "Default")
      (node (ref "X-SOUTH") (pin "14") (pinfunction "14_14") (pintype "bidirectional"))
    )
    (net (code "188") (name "S01_N") (class "Default")
      (node (ref "X-SOUTH") (pin "17") (pinfunction "17_17") (pintype "bidirectional"))
    )
    (net (code "189") (name "S01_P") (class "Default")
      (node (ref "X-SOUTH") (pin "15") (pinfunction "15_15") (pintype "bidirectional"))
    )
    (net (code "190") (name "S02_N") (class "Default")
      (node (ref "X-SOUTH") (pin "22") (pinfunction "22_22") (pintype "bidirectional"))
    )
    (net (code "191") (name "S02_P") (class "Default")
      (node (ref "X-SOUTH") (pin "20") (pinfunction "20_20") (pintype "bidirectional"))
    )
    (net (code "192") (name "S03_N") (class "Default")
      (node (ref "X-SOUTH") (pin "23") (pinfunction "23_23") (pintype "bidirectional"))
    )
    (net (code "193") (name "S03_P") (class "Default")
      (node (ref "X-SOUTH") (pin "21") (pinfunction "21_21") (pintype "bidirectional"))
    )
    (net (code "194") (name "S05_N") (class "Default")
      (node (ref "X-SOUTH") (pin "29") (pinfunction "29_29") (pintype "bidirectional"))
    )
    (net (code "195") (name "S05_P") (class "Default")
      (node (ref "X-SOUTH") (pin "27") (pinfunction "27_27") (pintype "bidirectional"))
    )
    (net (code "196") (name "S38_N") (class "Default")
      (node (ref "X-SOUTH") (pin "130") (pinfunction "130_130") (pintype "bidirectional"))
    )
    (net (code "197") (name "S38_P") (class "Default")
      (node (ref "X-SOUTH") (pin "128") (pinfunction "128_128") (pintype "bidirectional"))
    )
    (net (code "198") (name "S39_N") (class "Default")
      (node (ref "X-SOUTH") (pin "131") (pinfunction "131_131") (pintype "bidirectional"))
    )
    (net (code "199") (name "S39_P") (class "Default")
      (node (ref "X-SOUTH") (pin "129") (pinfunction "129_129") (pintype "bidirectional"))
    )
    (net (code "200") (name "SYS_RES_N") (class "Default")
      (node (ref "X-EAST") (pin "22") (pinfunction "22_22") (pintype "bidirectional"))
      (node (ref "X-NORTH") (pin "125") (pinfunction "125_125") (pintype "bidirectional"))
    )
    (net (code "201") (name "S_CHK_EN") (class "Default")
      (node (ref "X-EAST") (pin "94") (pinfunction "94_94") (pintype "bidirectional"))
      (node (ref "X-SOUTH") (pin "8") (pinfunction "8_8") (pintype "bidirectional"))
    )
    (net (code "202") (name "S_CHK_V") (class "Default")
      (node (ref "X-EAST") (pin "92") (pinfunction "92_92") (pintype "bidirectional"))
      (node (ref "X-SOUTH") (pin "10") (pinfunction "10_10") (pintype "bidirectional"))
    )
    (net (code "203") (name "S_I2C_EN") (class "Default")
      (node (ref "X-SOUTH") (pin "137") (pinfunction "137_137") (pintype "bidirectional"))
      (node (ref "X-WEST") (pin "7") (pinfunction "7_7") (pintype "bidirectional"))
    )
    (net (code "204") (name "S_I2C_V") (class "Default")
      (node (ref "X-SOUTH") (pin "135") (pinfunction "135_135") (pintype "bidirectional"))
      (node (ref "X-WEST") (pin "9") (pinfunction "9_9") (pintype "bidirectional"))
    )
    (net (code "205") (name "S_SCK") (class "Default")
      (node (ref "X-SOUTH") (pin "144") (pinfunction "144_144") (pintype "bidirectional"))
      (node (ref "X-WEST") (pin "2") (pinfunction "2_2") (pintype "bidirectional"))
    )
    (net (code "206") (name "S_SCL") (class "Default")
      (node (ref "X-SOUTH") (pin "143") (pinfunction "143_143") (pintype "bidirectional"))
      (node (ref "X-WEST") (pin "1") (pinfunction "1_1") (pintype "bidirectional"))
    )
    (net (code "207") (name "S_SDA") (class "Default")
      (node (ref "X-SOUTH") (pin "141") (pinfunction "141_141") (pintype "bidirectional"))
      (node (ref "X-WEST") (pin "3") (pinfunction "3_3") (pintype "bidirectional"))
    )
    (net (code "208") (name "S_SDI") (class "Default")
      (node (ref "X-SOUTH") (pin "140") (pinfunction "140_140") (pintype "bidirectional"))
      (node (ref "X-WEST") (pin "6") (pinfunction "6_6") (pintype "bidirectional"))
    )
    (net (code "209") (name "S_SDO") (class "Default")
      (node (ref "X-SOUTH") (pin "142") (pinfunction "142_142") (pintype "bidirectional"))
      (node (ref "X-WEST") (pin "4") (pinfunction "4_4") (pintype "bidirectional"))
    )
    (net (code "210") (name "S_SPI_EN") (class "Default")
      (node (ref "X-SOUTH") (pin "136") (pinfunction "136_136") (pintype "bidirectional"))
      (node (ref "X-WEST") (pin "8") (pinfunction "8_8") (pintype "bidirectional"))
    )
    (net (code "211") (name "S_SPI_V") (class "Default")
      (node (ref "X-SOUTH") (pin "134") (pinfunction "134_134") (pintype "bidirectional"))
      (node (ref "X-WEST") (pin "10") (pinfunction "10_10") (pintype "bidirectional"))
    )
    (net (code "212") (name "S_VE") (class "Default")
      (node (ref "C7") (pin "1") (pinfunction "1_1") (pintype "passive"))
      (node (ref "SE") (pin "1") (pinfunction "1_1") (pintype "passive"))
      (node (ref "X-SOUTH") (pin "13") (pinfunction "13_13") (pintype "bidirectional"))
      (node (ref "X-SOUTH") (pin "19") (pinfunction "19_19") (pintype "bidirectional"))
      (node (ref "X-SOUTH") (pin "31") (pinfunction "31_31") (pintype "bidirectional"))
      (node (ref "X-SOUTH") (pin "37") (pinfunction "37_37") (pintype "bidirectional"))
    )
    (net (code "213") (name "S_VE_CV") (class "Default")
      (node (ref "X-EAST") (pin "100") (pinfunction "100_100") (pintype "bidirectional"))
      (node (ref "X-SOUTH") (pin "2") (pinfunction "2_2") (pintype "bidirectional"))
    )
    (net (code "214") (name "S_VE_OV") (class "Default")
      (node (ref "X-EAST") (pin "99") (pinfunction "99_99") (pintype "bidirectional"))
      (node (ref "X-SOUTH") (pin "1") (pinfunction "1_1") (pintype "bidirectional"))
    )
    (net (code "215") (name "S_VE_RS") (class "Default")
      (node (ref "X-EAST") (pin "84") (pinfunction "84_84") (pintype "bidirectional"))
      (node (ref "X-SOUTH") (pin "25") (pinfunction "25_25") (pintype "bidirectional"))
    )
    (net (code "216") (name "S_VE_UV") (class "Default")
      (node (ref "X-EAST") (pin "89") (pinfunction "89_89") (pintype "bidirectional"))
      (node (ref "X-SOUTH") (pin "7") (pinfunction "7_7") (pintype "bidirectional"))
    )
    (net (code "217") (name "S_VS") (class "Default")
      (node (ref "C6") (pin "1") (pinfunction "1_1") (pintype "passive"))
      (node (ref "SW") (pin "1") (pinfunction "1_1") (pintype "passive"))
      (node (ref "X-SOUTH") (pin "49") (pinfunction "49_49") (pintype "bidirectional"))
      (node (ref "X-SOUTH") (pin "55") (pinfunction "55_55") (pintype "bidirectional"))
      (node (ref "X-SOUTH") (pin "61") (pinfunction "61_61") (pintype "bidirectional"))
      (node (ref "X-SOUTH") (pin "67") (pinfunction "67_67") (pintype "bidirectional"))
      (node (ref "X-SOUTH") (pin "79") (pinfunction "79_79") (pintype "bidirectional"))
      (node (ref "X-SOUTH") (pin "85") (pinfunction "85_85") (pintype "bidirectional"))
      (node (ref "X-SOUTH") (pin "91") (pinfunction "91_91") (pintype "bidirectional"))
      (node (ref "X-SOUTH") (pin "97") (pinfunction "97_97") (pintype "bidirectional"))
    )
    (net (code "218") (name "S_VS_CV") (class "Default")
      (node (ref "X-EAST") (pin "98") (pinfunction "98_98") (pintype "bidirectional"))
      (node (ref "X-SOUTH") (pin "4") (pinfunction "4_4") (pintype "bidirectional"))
    )
    (net (code "219") (name "S_VS_OV") (class "Default")
      (node (ref "X-EAST") (pin "97") (pinfunction "97_97") (pintype "bidirectional"))
      (node (ref "X-SOUTH") (pin "3") (pinfunction "3_3") (pintype "bidirectional"))
    )
    (net (code "220") (name "S_VS_RS") (class "Default")
      (node (ref "X-EAST") (pin "86") (pinfunction "86_86") (pintype "bidirectional"))
      (node (ref "X-SOUTH") (pin "73") (pinfunction "73_73") (pintype "bidirectional"))
    )
    (net (code "221") (name "S_VS_UV") (class "Default")
      (node (ref "X-EAST") (pin "87") (pinfunction "87_87") (pintype "bidirectional"))
      (node (ref "X-SOUTH") (pin "9") (pinfunction "9_9") (pintype "bidirectional"))
    )
    (net (code "222") (name "S_VW") (class "Default")
      (node (ref "C2") (pin "1") (pinfunction "1_1") (pintype "passive"))
      (node (ref "SW") (pin "2") (pinfunction "2_2") (pintype "passive"))
      (node (ref "X-SOUTH") (pin "109") (pinfunction "109_109") (pintype "bidirectional"))
      (node (ref "X-SOUTH") (pin "115") (pinfunction "115_115") (pintype "bidirectional"))
      (node (ref "X-SOUTH") (pin "127") (pinfunction "127_127") (pintype "bidirectional"))
      (node (ref "X-SOUTH") (pin "133") (pinfunction "133_133") (pintype "bidirectional"))
    )
    (net (code "223") (name "S_VW_CV") (class "Default")
      (node (ref "X-EAST") (pin "96") (pinfunction "96_96") (pintype "bidirectional"))
      (node (ref "X-SOUTH") (pin "6") (pinfunction "6_6") (pintype "bidirectional"))
    )
    (net (code "224") (name "S_VW_OV") (class "Default")
      (node (ref "X-EAST") (pin "95") (pinfunction "95_95") (pintype "bidirectional"))
      (node (ref "X-SOUTH") (pin "5") (pinfunction "5_5") (pintype "bidirectional"))
    )
    (net (code "225") (name "S_VW_RS") (class "Default")
      (node (ref "X-EAST") (pin "88") (pinfunction "88_88") (pintype "bidirectional"))
      (node (ref "X-SOUTH") (pin "121") (pinfunction "121_121") (pintype "bidirectional"))
    )
    (net (code "226") (name "S_VW_UV") (class "Default")
      (node (ref "X-EAST") (pin "85") (pinfunction "85_85") (pintype "bidirectional"))
      (node (ref "X-SOUTH") (pin "11") (pinfunction "11_11") (pintype "bidirectional"))
    )
    (net (code "227") (name "TCK") (class "Default")
      (node (ref "X-WEST") (pin "12") (pinfunction "12_12") (pintype "bidirectional"))
    )
    (net (code "228") (name "TDI") (class "Default")
      (node (ref "X-WEST") (pin "16") (pinfunction "16_16") (pintype "bidirectional"))
    )
    (net (code "229") (name "TDIG1") (class "Default")
      (node (ref "X-EAST") (pin "18") (pinfunction "18_18") (pintype "bidirectional"))
      (node (ref "X-NORTH") (pin "123") (pinfunction "123_123") (pintype "bidirectional"))
    )
    (net (code "230") (name "TDIG2") (class "Default")
      (node (ref "X-NORTH") (pin "130") (pinfunction "130_130") (pintype "bidirectional"))
    )
    (net (code "231") (name "TDO") (class "Default")
      (node (ref "X-WEST") (pin "18") (pinfunction "18_18") (pintype "bidirectional"))
    )
    (net (code "232") (name "TMS") (class "Default")
      (node (ref "X-WEST") (pin "14") (pinfunction "14_14") (pintype "bidirectional"))
    )
    (net (code "233") (name "TP9") (class "Default")
      (node (ref "X-NORTH") (pin "119") (pinfunction "119_119") (pintype "bidirectional"))
    )
    (net (code "234") (name "T_EXP1") (class "Default")
      (node (ref "X-EAST") (pin "12") (pinfunction "12_12") (pintype "bidirectional"))
      (node (ref "X-NORTH") (pin "131") (pinfunction "131_131") (pintype "bidirectional"))
    )
    (net (code "235") (name "T_EXP2") (class "Default")
      (node (ref "X-EAST") (pin "16") (pinfunction "16_16") (pintype "bidirectional"))
      (node (ref "X-NORTH") (pin "117") (pinfunction "117_117") (pintype "bidirectional"))
    )
    (net (code "236") (name "W_EN") (class "Default")
      (node (ref "X-WEST") (pin "19") (pinfunction "19_19") (pintype "bidirectional"))
    )
    (net (code "237") (name "W_I2C_EN") (class "Default")
      (node (ref "X-WEST") (pin "13") (pinfunction "13_13") (pintype "bidirectional"))
    )
    (net (code "238") (name "W_I2C_V") (class "Default")
      (node (ref "X-WEST") (pin "11") (pinfunction "11_11") (pintype "bidirectional"))
    )
    (net (code "239") (name "W_SCL") (class "Default")
      (node (ref "X-WEST") (pin "15") (pinfunction "15_15") (pintype "bidirectional"))
    )
    (net (code "240") (name "W_SDA") (class "Default")
      (node (ref "X-WEST") (pin "17") (pinfunction "17_17") (pintype "bidirectional"))
    )
    (net (code "241") (name "W_VW") (class "Default")
      (node (ref "C8") (pin "1") (pinfunction "1_1") (pintype "passive"))
      (node (ref "NW") (pin "2") (pinfunction "2_2") (pintype "passive"))
    )
    (net (code "242") (name "W_VW_CV") (class "Default")
      (node (ref "X-WEST") (pin "90") (pinfunction "90_90") (pintype "bidirectional"))
    )
    (net (code "243") (name "W_VW_OV") (class "Default")
      (node (ref "X-WEST") (pin "93") (pinfunction "93_93") (pintype "bidirectional"))
    )
    (net (code "244") (name "W_VW_UV") (class "Default")
      (node (ref "X-WEST") (pin "91") (pinfunction "91_91") (pintype "bidirectional"))
    )
    (net (code "245") (name "unconnected-(X-EAST-PadM1)") (class "Default")
      (node (ref "X-EAST") (pin "M1") (pinfunction "M1_M1") (pintype "bidirectional"))
    )
    (net (code "246") (name "unconnected-(X-EAST-PadM2)") (class "Default")
      (node (ref "X-EAST") (pin "M2") (pinfunction "M2_M2") (pintype "bidirectional"))
    )
    (net (code "247") (name "unconnected-(X-NORTH-PadM1)") (class "Default")
      (node (ref "X-NORTH") (pin "M1") (pinfunction "M1_M1") (pintype "bidirectional"))
    )
    (net (code "248") (name "unconnected-(X-NORTH-PadM2)") (class "Default")
      (node (ref "X-NORTH") (pin "M2") (pinfunction "M2_M2") (pintype "bidirectional"))
    )
    (net (code "249") (name "unconnected-(X-SOUTH-PadM1)") (class "Default")
      (node (ref "X-SOUTH") (pin "M1") (pinfunction "M1_M1") (pintype "bidirectional"))
    )
    (net (code "250") (name "unconnected-(X-SOUTH-PadM2)") (class "Default")
      (node (ref "X-SOUTH") (pin "M2") (pinfunction "M2_M2") (pintype "bidirectional"))
    )
    (net (code "251") (name "unconnected-(X-WEST-PadM1)") (class "Default")
      (node (ref "X-WEST") (pin "M1") (pinfunction "M1_M1") (pintype "bidirectional"))
    )
    (net (code "252") (name "unconnected-(X-WEST-PadM2)") (class "Default")
      (node (ref "X-WEST") (pin "M2") (pinfunction "M2_M2") (pintype "bidirectional"))
    )
  )
)
